# 4_-Battery.net
KiCad netlist of a schematic drawn in Altium Designer
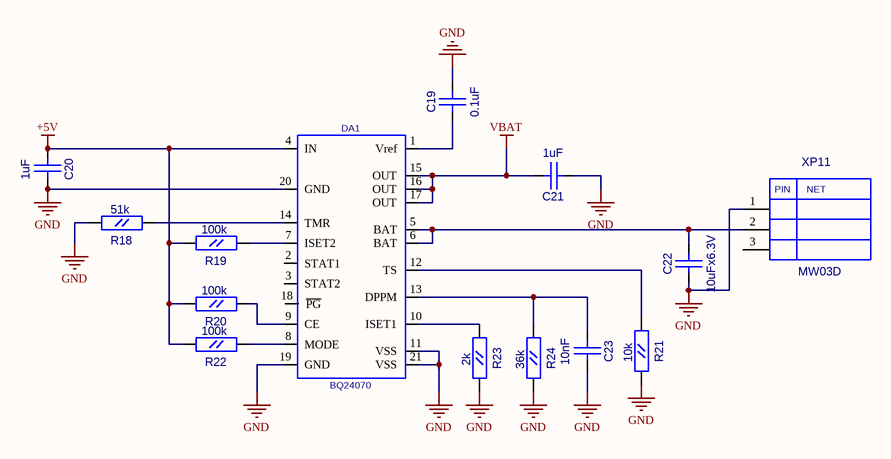
[diagram p0: [4]-Battery.SchDoc]

(export (version "E")
  (design (tool "Eeschema 10.0.6"))
  (components
    (comp (ref "C19")
      (value "0.1uF")
      (footprint "CC0603")
      (description "CC0603")
      (libsource (lib "gprs_modem_2") (part "CC0603"))
    )
    (comp (ref "C20")
      (value "1uF")
      (footprint "CC0603")
      (description "CC0603")
      (libsource (lib "gprs_modem_2") (part "CC0603"))
    )
    (comp (ref "C21")
      (value "1uF")
      (footprint "CC0603")
      (description "CC0603")
      (libsource (lib "gprs_modem_2") (part "CC0603"))
    )
    (comp (ref "C22")
      (value "10uFx6.3V")
      (footprint "CC0805")
      (description "CC0805")
      (libsource (lib "gprs_modem_2") (part "CC0805"))
    )
    (comp (ref "C23")
      (value "10nF")
      (footprint "CC0603")
      (description "CC0603")
      (libsource (lib "gprs_modem_2") (part "CC0603"))
    )
    (comp (ref "DA1")
      (value "BQ24070")
      (footprint "P-PQFP-N20")
      (libsource (lib "gprs_modem") (part "BQ24070"))
    )
    (comp (ref "R18")
      (value "51k")
      (footprint "RC0603")
      (description "RC0603")
      (libsource (lib "gprs_modem_2") (part "RC0603"))
    )
    (comp (ref "R19")
      (value "100k")
      (footprint "RC0603")
      (description "RC0603")
      (libsource (lib "gprs_modem_2") (part "RC0603"))
    )
    (comp (ref "R20")
      (value "100k")
      (footprint "RC0603")
      (description "RC0603")
      (libsource (lib "gprs_modem_2") (part "RC0603"))
    )
    (comp (ref "R21")
      (value "10k")
      (footprint "RC0603")
      (description "RC0603")
      (libsource (lib "gprs_modem_2") (part "RC0603"))
    )
    (comp (ref "R22")
      (value "100k")
      (footprint "RC0603")
      (description "RC0603")
      (libsource (lib "gprs_modem_2") (part "RC0603"))
    )
    (comp (ref "R23")
      (value "2k")
      (footprint "RC0603")
      (description "RC0603")
      (libsource (lib "gprs_modem_2") (part "RC0603"))
    )
    (comp (ref "R24")
      (value "36k")
      (footprint "RC0603")
      (description "RC0603")
      (libsource (lib "gprs_modem_2") (part "RC0603"))
    )
    (comp (ref "XP11") (value "MW03D") (footprint "MW03D") (libsource (lib "gprs_modem") (part "MW03D")))
  )
  (nets
    (net (code "1") (name "+5V") (class "Default")
      (node (ref "C20") (pin "1") (pinfunction "A_1") (pintype "passive"))
      (node (ref "DA1") (pin "4") (pinfunction "IN_4") (pintype "passive"))
      (node (ref "R19") (pin "2") (pinfunction "B_2") (pintype "passive"))
      (node (ref "R20") (pin "2") (pinfunction "B_2") (pintype "passive"))
      (node (ref "R22") (pin "2") (pinfunction "B_2") (pintype "passive"))
    )
    (net (code "2") (name "GND") (class "Default")
      (node (ref "C19") (pin "2") (pinfunction "B_2") (pintype "passive"))
      (node (ref "C20") (pin "2") (pinfunction "B_2") (pintype "passive"))
      (node (ref "C21") (pin "1") (pinfunction "A_1") (pintype "passive"))
      (node (ref "C22") (pin "1") (pinfunction "A_1") (pintype "passive"))
      (node (ref "C23") (pin "2") (pinfunction "B_2") (pintype "passive"))
      (node (ref "DA1") (pin "11") (pinfunction "VSS_11") (pintype "passive"))
      (node (ref "DA1") (pin "19") (pinfunction "GND_19") (pintype "passive"))
      (node (ref "DA1") (pin "20") (pinfunction "GND_20") (pintype "passive"))
      (node (ref "DA1") (pin "21") (pinfunction "VSS_21") (pintype "passive"))
      (node (ref "R18") (pin "2") (pinfunction "B_2") (pintype "passive"))
      (node (ref "R21") (pin "2") (pinfunction "B_2") (pintype "passive"))
      (node (ref "R23") (pin "2") (pinfunction "B_2") (pintype "passive"))
      (node (ref "R24") (pin "2") (pinfunction "B_2") (pintype "passive"))
      (node (ref "XP11") (pin "1") (pinfunction "1_1") (pintype "passive"))
    )
    (net (code "3") (name "Net-(C19-A)") (class "Default")
      (node (ref "C19") (pin "1") (pinfunction "A_1") (pintype "passive"))
      (node (ref "DA1") (pin "1") (pinfunction "Vref_1") (pintype "passive"))
    )
    (net (code "4") (name "Net-(C22-B)") (class "Default")
      (node (ref "C22") (pin "2") (pinfunction "B_2") (pintype "passive"))
      (node (ref "DA1") (pin "5") (pinfunction "BAT_5") (pintype "passive"))
      (node (ref "DA1") (pin "6") (pinfunction "BAT_6") (pintype "passive"))
      (node (ref "XP11") (pin "2") (pinfunction "2_2") (pintype "passive"))
    )
    (net (code "5") (name "Net-(C23-A)") (class "Default")
      (node (ref "C23") (pin "1") (pinfunction "A_1") (pintype "passive"))
      (node (ref "DA1") (pin "13") (pinfunction "DPPM_13") (pintype "passive"))
      (node (ref "R24") (pin "1") (pinfunction "A_1") (pintype "passive"))
    )
    (net (code "6") (name "Net-(DA1-CE)") (class "Default")
      (node (ref "DA1") (pin "9") (pinfunction "CE_9") (pintype "passive"))
      (node (ref "R20") (pin "1") (pinfunction "A_1") (pintype "passive"))
    )
    (net (code "7") (name "Net-(DA1-ISET1)") (class "Default")
      (node (ref "DA1") (pin "10") (pinfunction "ISET1_10") (pintype "passive"))
      (node (ref "R23") (pin "1") (pinfunction "A_1") (pintype "passive"))
    )
    (net (code "8") (name "Net-(DA1-ISET2)") (class "Default")
      (node (ref "DA1") (pin "7") (pinfunction "ISET2_7") (pintype "passive"))
      (node (ref "R19") (pin "1") (pinfunction "A_1") (pintype "passive"))
    )
    (net (code "9") (name "Net-(DA1-MODE)") (class "Default")
      (node (ref "DA1") (pin "8") (pinfunction "MODE_8") (pintype "passive"))
      (node (ref "R22") (pin "1") (pinfunction "A_1") (pintype "passive"))
    )
    (net (code "10") (name "Net-(DA1-TMR)") (class "Default")
      (node (ref "DA1") (pin "14") (pinfunction "TMR_14") (pintype "passive"))
      (node (ref "R18") (pin "1") (pinfunction "A_1") (pintype "passive"))
    )
    (net (code "11") (name "Net-(DA1-TS)") (class "Default")
      (node (ref "DA1") (pin "12") (pinfunction "TS_12") (pintype "passive"))
      (node (ref "R21") (pin "1") (pinfunction "A_1") (pintype "passive"))
    )
    (net (code "12") (name "VBAT") (class "Default")
      (node (ref "C21") (pin "2") (pinfunction "B_2") (pintype "passive"))
      (node (ref "DA1") (pin "15") (pinfunction "OUT_15") (pintype "passive"))
      (node (ref "DA1") (pin "16") (pinfunction "OUT_16") (pintype "passive"))
      (node (ref "DA1") (pin "17") (pinfunction "OUT_17") (pintype "passive"))
    )
    (net (code "13") (name "unconnected-(DA1-STAT1-Pad2)") (class "Default")
      (node (ref "DA1") (pin "2") (pinfunction "STAT1_2") (pintype "passive"))
    )
    (net (code "14") (name "unconnected-(DA1-STAT2-Pad3)") (class "Default")
      (node (ref "DA1") (pin "3") (pinfunction "STAT2_3") (pintype "passive"))
    )
    (net (code "15") (name "unconnected-(DA1-~{PG}-Pad18)") (class "Default")
      (node (ref "DA1") (pin "18") (pinfunction "~{PG}_18") (pintype "passive"))
    )
    (net (code "16") (name "unconnected-(XP11-Pad3)") (class "Default")
      (node (ref "XP11") (pin "3") (pinfunction "3_3") (pintype "passive"))
    )
  )
)
